# C-02_LvDDR3.net
KiCad netlist of a schematic drawn in Altium Designer
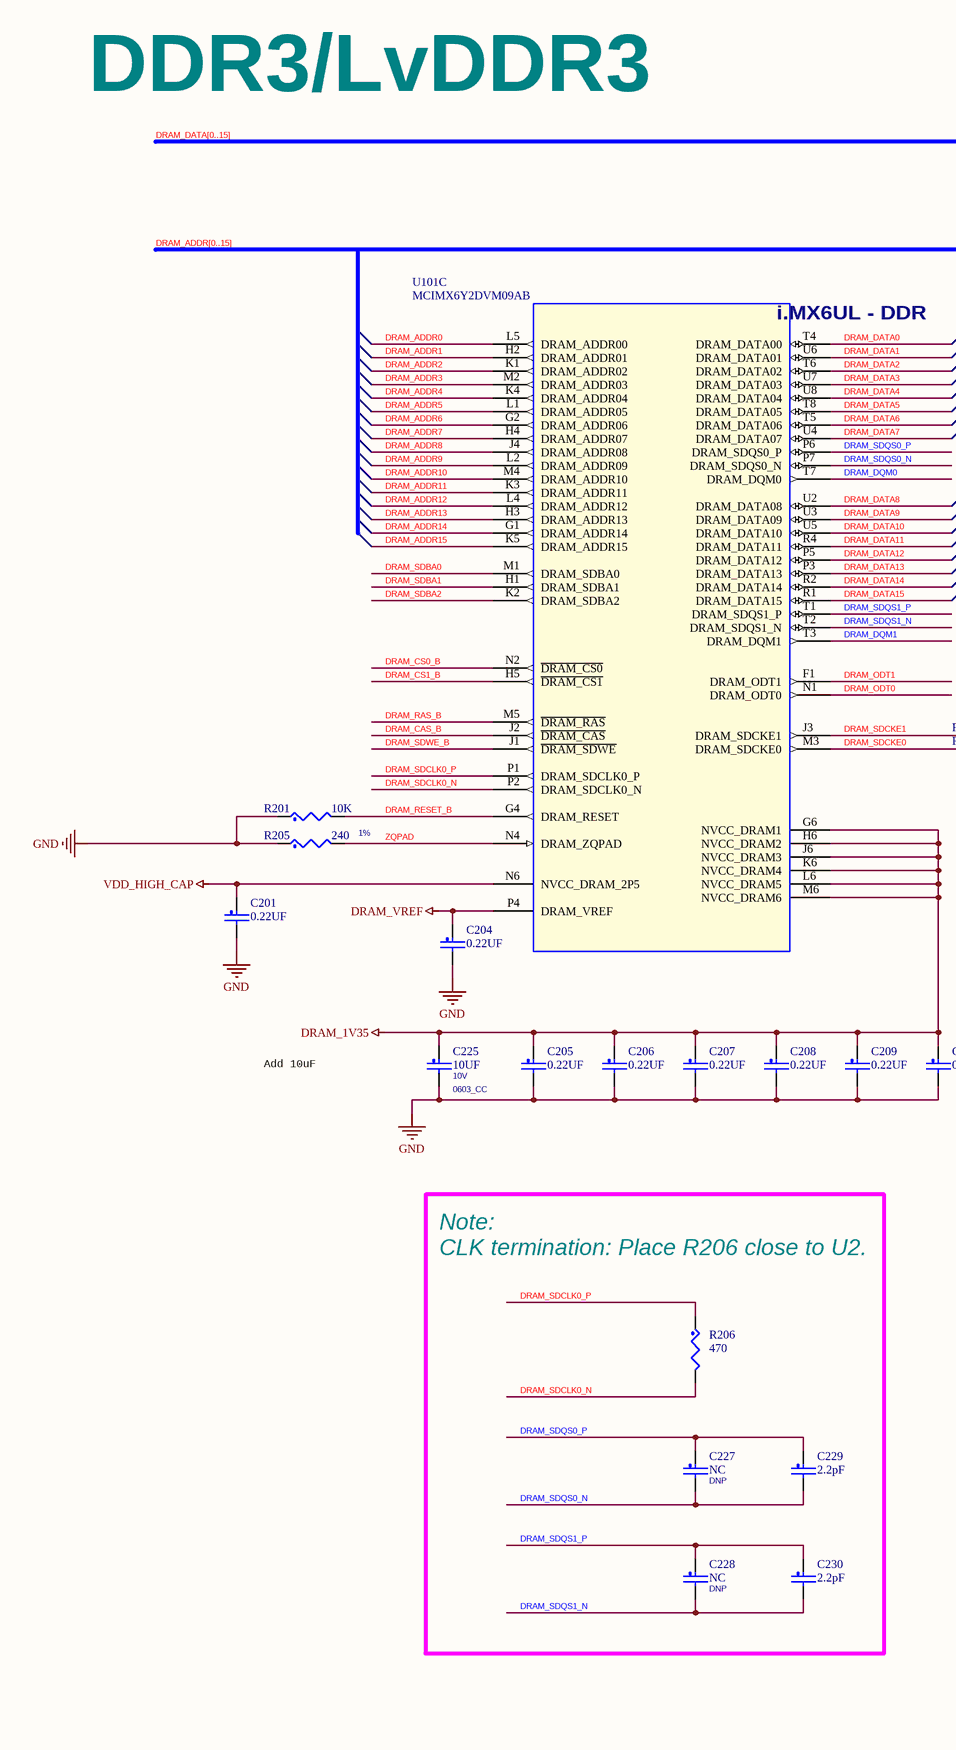
[diagram p0: C-02 LvDDR3.SchDoc, left]
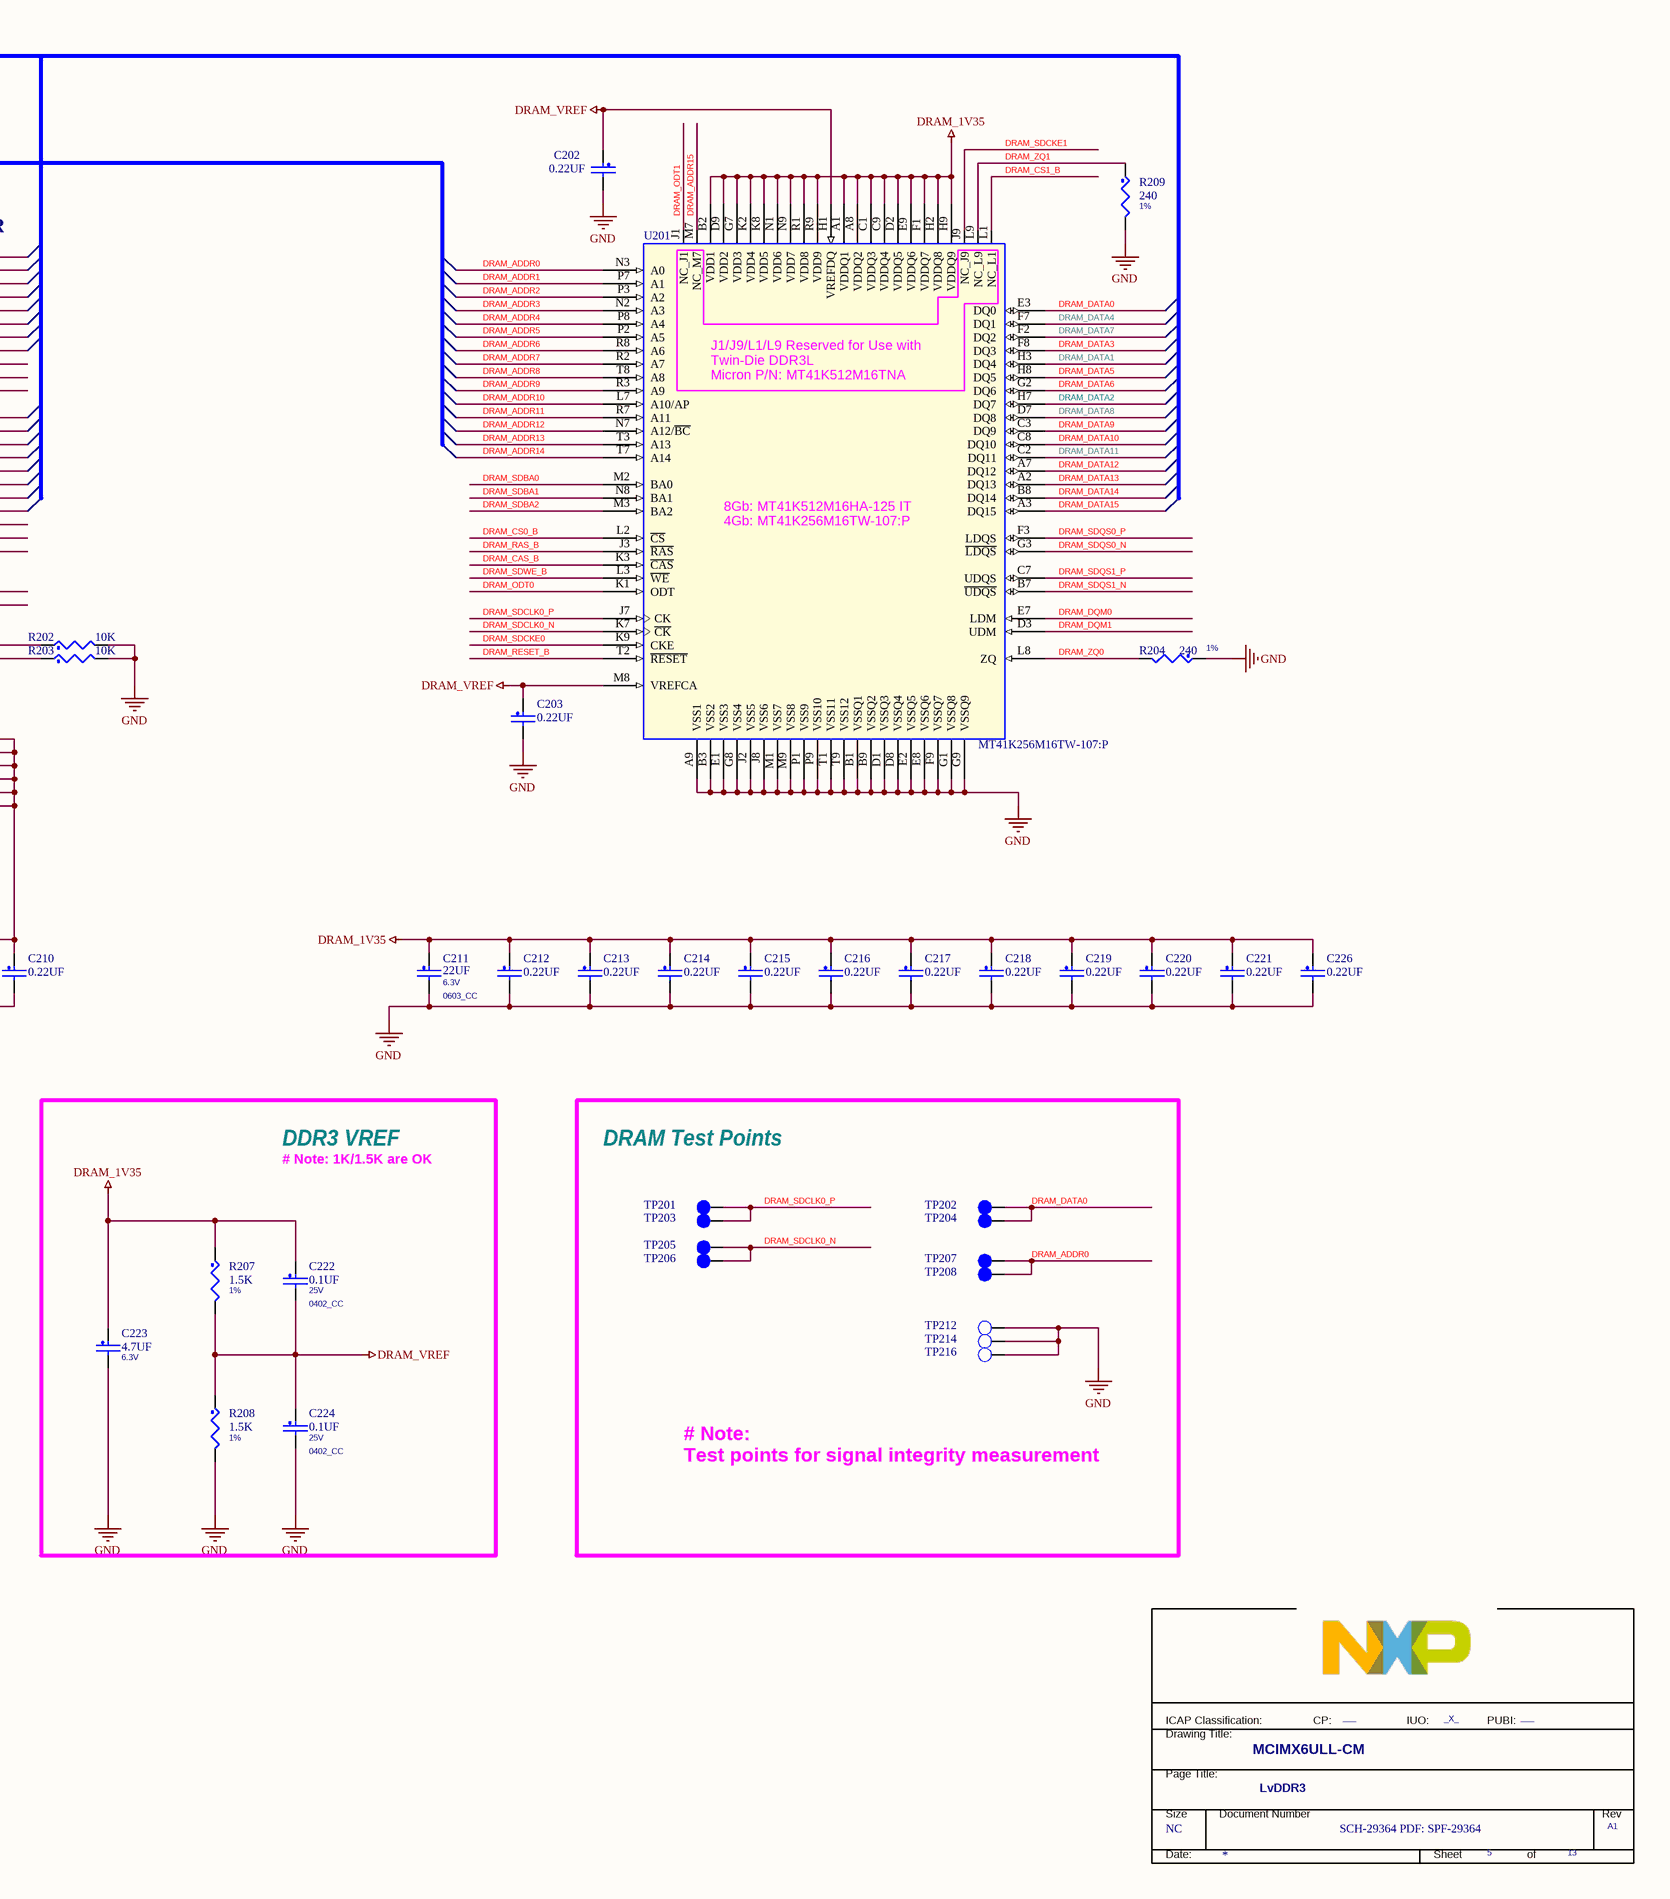
[diagram p1: C-02 LvDDR3.SchDoc, right]

(export (version "E")
  (design (tool "Eeschema 10.0.6"))
  (components
    (comp (ref "*")
      (value "TitleBlock_FS")
      (fields
        (field (name "PAGETITLE") "LvDDR3")
        (field (name "PAGE COUNT") "13")
        (field (name "PAGE NUMBER") "5")
        (field (name "PAGE SIZE") "NC")
        (field (name "TITLE") "MCIMX6ULL-CM")
        (field (name "REVCODE") "A1")
        (field (name "DOC") "SCH-29364 PDF: SPF-29364")
        (field (name "FCP") "___")
        (field (name "PUBI") "___")
        (field (name "FIUO") "_X_")
      )
      (libsource (lib "*") (part "TitleBlock_FS"))
    )
    (comp (ref "C201")
      (value "0.22UF")
      (footprint "0402T_C")
      (description "CAP CER 0.22UF 10V 10% X5R 0402")
      (fields (field (name "VOLTAGE") "10V") (field (name "TOLERANCE") "10%"))
      (libsource (lib "*") (part "CAP_NP"))
    )
    (comp (ref "C202")
      (value "0.22UF")
      (footprint "0402T_C")
      (description "CAP CER 0.22UF 10V 10% X5R 0402")
      (fields (field (name "TOLERANCE") "10%") (field (name "VOLTAGE") "10V"))
      (libsource (lib "*") (part "CAP_NP"))
    )
    (comp (ref "C203")
      (value "0.22UF")
      (footprint "0402T_C")
      (description "CAP CER 0.22UF 10V 10% X5R 0402")
      (fields (field (name "TOLERANCE") "10%") (field (name "VOLTAGE") "10V"))
      (libsource (lib "*") (part "CAP_NP"))
    )
    (comp (ref "C204")
      (value "0.22UF")
      (footprint "0402T_C")
      (description "CAP CER 0.22UF 10V 10% X5R 0402")
      (fields (field (name "TOLERANCE") "10%") (field (name "VOLTAGE") "10V"))
      (libsource (lib "*") (part "CAP_NP"))
    )
    (comp (ref "C205")
      (value "0.22UF")
      (footprint "0402T_C")
      (description "CAP CER 0.22UF 10V 10% X5R 0402")
      (fields (field (name "VOLTAGE") "10V") (field (name "TOLERANCE") "10%"))
      (libsource (lib "*") (part "CAP_NP"))
    )
    (comp (ref "C206")
      (value "0.22UF")
      (footprint "0402T_C")
      (description "CAP CER 0.22UF 10V 10% X5R 0402")
      (fields (field (name "VOLTAGE") "10V") (field (name "TOLERANCE") "10%"))
      (libsource (lib "*") (part "CAP_NP"))
    )
    (comp (ref "C207")
      (value "0.22UF")
      (footprint "0402T_C")
      (description "CAP CER 0.22UF 10V 10% X5R 0402")
      (fields (field (name "VOLTAGE") "10V") (field (name "TOLERANCE") "10%"))
      (libsource (lib "*") (part "CAP_NP"))
    )
    (comp (ref "C208")
      (value "0.22UF")
      (footprint "0402T_C")
      (description "CAP CER 0.22UF 10V 10% X5R 0402")
      (fields (field (name "VOLTAGE") "10V") (field (name "TOLERANCE") "10%"))
      (libsource (lib "*") (part "CAP_NP"))
    )
    (comp (ref "C209")
      (value "0.22UF")
      (footprint "0402T_C")
      (description "CAP CER 0.22UF 10V 10% X5R 0402")
      (fields (field (name "VOLTAGE") "10V") (field (name "TOLERANCE") "10%"))
      (libsource (lib "*") (part "CAP_NP"))
    )
    (comp (ref "C210")
      (value "0.22UF")
      (footprint "0402T_C")
      (description "CAP CER 0.22UF 10V 10% X5R 0402")
      (fields (field (name "TOLERANCE") "10%") (field (name "VOLTAGE") "10V"))
      (libsource (lib "*") (part "CAP_NP"))
    )
    (comp (ref "C211")
      (value "22UF")
      (footprint "0603_CC")
      (description "CAP CER 22UF 6.3V 20% X5R 0603")
      (fields
        (field (name "VOLTAGE RATING") "6.3V")
        (field (name "TOLERANCE") "20%")
        (field (name "VOLTAGE") "6.3V")
        (field (name "PCB FOOTPRINT") "0603_CC")
      )
      (libsource (lib "*") (part "CAP_NP"))
    )
    (comp (ref "C212")
      (value "0.22UF")
      (footprint "0402T_C")
      (description "CAP CER 0.22UF 10V 10% X5R 0402")
      (fields (field (name "VOLTAGE") "10V") (field (name "TOLERANCE") "10%"))
      (libsource (lib "*") (part "CAP_NP"))
    )
    (comp (ref "C213")
      (value "0.22UF")
      (footprint "0402T_C")
      (description "CAP CER 0.22UF 10V 10% X5R 0402")
      (fields (field (name "VOLTAGE") "10V") (field (name "TOLERANCE") "10%"))
      (libsource (lib "*") (part "CAP_NP"))
    )
    (comp (ref "C214")
      (value "0.22UF")
      (footprint "0402T_C")
      (description "CAP CER 0.22UF 10V 10% X5R 0402")
      (fields (field (name "VOLTAGE") "10V") (field (name "TOLERANCE") "10%"))
      (libsource (lib "*") (part "CAP_NP"))
    )
    (comp (ref "C215")
      (value "0.22UF")
      (footprint "0402T_C")
      (description "CAP CER 0.22UF 10V 10% X5R 0402")
      (fields (field (name "VOLTAGE") "10V") (field (name "TOLERANCE") "10%"))
      (libsource (lib "*") (part "CAP_NP"))
    )
    (comp (ref "C216")
      (value "0.22UF")
      (footprint "0402T_C")
      (description "CAP CER 0.22UF 10V 10% X5R 0402")
      (fields (field (name "VOLTAGE") "10V") (field (name "TOLERANCE") "10%"))
      (libsource (lib "*") (part "CAP_NP"))
    )
    (comp (ref "C217")
      (value "0.22UF")
      (footprint "0402T_C")
      (description "CAP CER 0.22UF 10V 10% X5R 0402")
      (fields (field (name "TOLERANCE") "10%") (field (name "VOLTAGE") "10V"))
      (libsource (lib "*") (part "CAP_NP"))
    )
    (comp (ref "C218")
      (value "0.22UF")
      (footprint "0402T_C")
      (description "CAP CER 0.22UF 10V 10% X5R 0402")
      (fields (field (name "TOLERANCE") "10%") (field (name "VOLTAGE") "10V"))
      (libsource (lib "*") (part "CAP_NP"))
    )
    (comp (ref "C219")
      (value "0.22UF")
      (footprint "0402T_C")
      (description "CAP CER 0.22UF 10V 10% X5R 0402")
      (fields (field (name "TOLERANCE") "10%") (field (name "VOLTAGE") "10V"))
      (libsource (lib "*") (part "CAP_NP"))
    )
    (comp (ref "C220")
      (value "0.22UF")
      (footprint "0402T_C")
      (description "CAP CER 0.22UF 10V 10% X5R 0402")
      (fields (field (name "TOLERANCE") "10%") (field (name "VOLTAGE") "10V"))
      (libsource (lib "*") (part "CAP_NP"))
    )
    (comp (ref "C221")
      (value "0.22UF")
      (footprint "0402T_C")
      (description "CAP CER 0.22UF 10V 10% X5R 0402")
      (fields (field (name "TOLERANCE") "10%") (field (name "VOLTAGE") "10V"))
      (libsource (lib "*") (part "CAP_NP"))
    )
    (comp (ref "C222")
      (value "0.1UF")
      (footprint "0402T_C")
      (description "CAP CER 0.1UF 25V 10% X5R 0402")
      (fields
        (field (name "TOLERANCE") "10%")
        (field (name "VOLTAGE") "25V")
        (field (name "PCB FOOTPRINT") "0402_CC")
      )
      (libsource (lib "*") (part "CAP_NP"))
    )
    (comp (ref "C223")
      (value "4.7UF")
      (footprint "0402T_C")
      (description "CAP CER 4.7UF 6.3V 20% X5R 0402")
      (fields
        (field (name "TOLERANCE") "20%")
        (field (name "VOLTAGE RATING") "6.3V")
        (field (name "VOLTAGE") "6.3V")
      )
      (libsource (lib "*") (part "CAP_NP"))
    )
    (comp (ref "C224")
      (value "0.1UF")
      (footprint "0402T_C")
      (description "CAP CER 0.1UF 25V 10% X5R 0402")
      (fields
        (field (name "TOLERANCE") "10%")
        (field (name "VOLTAGE") "25V")
        (field (name "PCB FOOTPRINT") "0402_CC")
      )
      (libsource (lib "*") (part "CAP_NP"))
    )
    (comp (ref "C225")
      (value "10UF")
      (footprint "0402T_C")
      (description "CAP CER 10UF 10V 20% X5R 0603")
      (fields (field (name "VOLTAGE") "10V") (field (name "PCB FOOTPRINT") "0603_CC"))
      (libsource (lib "*") (part "CAP_NP"))
    )
    (comp (ref "C226")
      (value "0.22UF")
      (footprint "0402T_C")
      (description "CAP CER 0.22UF 10V 10% X5R 0402")
      (fields (field (name "VOLTAGE") "10V") (field (name "TOLERANCE") "10%"))
      (libsource (lib "*") (part "CAP_NP"))
    )
    (comp (ref "C227")
      (value "NC")
      (footprint "0402T_C")
      (description "CAP CER 2.2pF 50V 0.25pF C0G 0402")
      (fields
        (field (name "ASSY_OPT") "DNP")
        (field (name "VOLTAGE") "50V")
        (field (name "TOLERANCE") "11.36%")
      )
      (libsource (lib "*") (part "CAP_NP"))
    )
    (comp (ref "C228")
      (value "NC")
      (footprint "0402T_C")
      (description "CAP CER 2.2pF 50V 0.25pF C0G 0402")
      (fields
        (field (name "ASSY_OPT") "DNP")
        (field (name "VOLTAGE") "50V")
        (field (name "TOLERANCE") "11.36%")
      )
      (libsource (lib "*") (part "CAP_NP"))
    )
    (comp (ref "C229")
      (value "2.2pF")
      (footprint "0402T_C")
      (description "CAP CER 2.2pF 50V 0.25pF C0G 0402")
      (fields (field (name "VOLTAGE") "50V") (field (name "TOLERANCE") "11.36%"))
      (libsource (lib "*") (part "CAP_NP"))
    )
    (comp (ref "C230")
      (value "2.2pF")
      (footprint "0402T_C")
      (description "CAP CER 2.2pF 50V 0.25pF C0G 0402")
      (fields (field (name "VOLTAGE") "50V") (field (name "TOLERANCE") "11.36%"))
      (libsource (lib "*") (part "CAP_NP"))
    )
    (comp (ref "R201")
      (value "10K")
      (footprint "0402T_C")
      (description "RES MF 10K 1/16W 5% 0402")
      (fields (field (name "TOLERANCE") "5%"))
      (libsource (lib "*") (part "RES"))
    )
    (comp (ref "R202")
      (value "10K")
      (footprint "0402T_C")
      (description "RES MF 10K 1/16W 5% 0402")
      (fields (field (name "TOLERANCE") "5%"))
      (libsource (lib "*") (part "RES"))
    )
    (comp (ref "R203")
      (value "10K")
      (footprint "0402T_C")
      (description "RES MF 10K 1/16W 5% 0402")
      (fields (field (name "TOLERANCE") "5%"))
      (libsource (lib "*") (part "RES"))
    )
    (comp (ref "R204")
      (value "240")
      (footprint "0402T_C")
      (description "RES MF 240 OHM 1/16W 1% 0402")
      (fields (field (name "TOLERANCE") "1%"))
      (libsource (lib "*") (part "RES"))
    )
    (comp (ref "R205")
      (value "240")
      (footprint "0402T_C")
      (description "RES MF 240 OHM 1/16W 1% 0402")
      (fields (field (name "TOLERANCE") "1%"))
      (libsource (lib "*") (part "RES"))
    )
    (comp (ref "R206")
      (value "470")
      (footprint "0402T_C")
      (description "RES MF 470 OHM 1/16W 5% 0402")
      (fields (field (name "TOLERANCE") "5%"))
      (libsource (lib "*") (part "RES"))
    )
    (comp (ref "R207")
      (value "1.5K")
      (footprint "0402T_C")
      (description "RES MF 1.5K 1/16W 1% 0402")
      (fields (field (name "TOLERANCE") "1%"))
      (libsource (lib "*") (part "RES"))
    )
    (comp (ref "R208")
      (value "1.5K")
      (footprint "0402T_C")
      (description "RES MF 1.5K 1/16W 1% 0402")
      (fields (field (name "TOLERANCE") "1%"))
      (libsource (lib "*") (part "RES"))
    )
    (comp (ref "R209")
      (value "240")
      (footprint "0402T_C")
      (description "RES MF 240 OHM 1/16W 1% 0402")
      (fields (field (name "TOLERANCE") "1%"))
      (libsource (lib "*") (part "RES"))
    )
    (comp (ref "TP201")
      (value "TPAD_015")
      (footprint "TPAD_015")
      (description "TEST POINT PAD 15MIL DIA SMT, NO PART TO ORDER")
      (libsource (lib "*") (part "TESTLOOP"))
    )
    (comp (ref "TP202")
      (value "TPAD_015")
      (footprint "TPAD_015")
      (description "TEST POINT PAD 15MIL DIA SMT, NO PART TO ORDER")
      (libsource (lib "*") (part "TESTLOOP"))
    )
    (comp (ref "TP203")
      (value "TPAD_015")
      (footprint "TPAD_015")
      (description "TEST POINT PAD 15MIL DIA SMT, NO PART TO ORDER")
      (libsource (lib "*") (part "TESTLOOP"))
    )
    (comp (ref "TP204")
      (value "TPAD_015")
      (footprint "TPAD_015")
      (description "TEST POINT PAD 15MIL DIA SMT, NO PART TO ORDER")
      (libsource (lib "*") (part "TESTLOOP"))
    )
    (comp (ref "TP205")
      (value "TPAD_015")
      (footprint "TPAD_015")
      (description "TEST POINT PAD 15MIL DIA SMT, NO PART TO ORDER")
      (libsource (lib "*") (part "TESTLOOP"))
    )
    (comp (ref "TP206")
      (value "TPAD_015")
      (footprint "TPAD_015")
      (description "TEST POINT PAD 15MIL DIA SMT, NO PART TO ORDER")
      (libsource (lib "*") (part "TESTLOOP"))
    )
    (comp (ref "TP207")
      (value "TPAD_015")
      (footprint "TPAD_015")
      (description "TEST POINT PAD 15MIL DIA SMT, NO PART TO ORDER")
      (libsource (lib "*") (part "TESTLOOP"))
    )
    (comp (ref "TP208")
      (value "TPAD_015")
      (footprint "TPAD_015")
      (description "TEST POINT PAD 15MIL DIA SMT, NO PART TO ORDER")
      (libsource (lib "*") (part "TESTLOOP"))
    )
    (comp (ref "TP212")
      (value "TP_35MIL")
      (footprint "testpoint_35mil")
      (description "TEST POINT PAD .035 SMT, no part to order")
      (libsource (lib "*") (part "T POINT R"))
    )
    (comp (ref "TP214")
      (value "TP_35MIL")
      (footprint "testpoint_35mil")
      (description "TEST POINT PAD .035 SMT, no part to order")
      (libsource (lib "*") (part "T POINT R"))
    )
    (comp (ref "TP216")
      (value "TP_35MIL")
      (footprint "testpoint_35mil")
      (description "TEST POINT PAD .035 SMT, no part to order")
      (libsource (lib "*") (part "T POINT R"))
    )
    (comp (ref "U101")
      (value "MCIMX6Y2DVM09AB")
      (footprint "BGA289_0P8_14X14")
      (description "IC CPU ARM COREA7 900MHZ 16BIT 3-3.6V PBGA289")
      (libsource (lib "*") (part "MCIMX6Y2DVM05AA_PBGA_289P"))
    )
    (comp (ref "U201")
      (value "MT41K256M16TW-107:P")
      (footprint "bga96_0p8_8p15x14p15")
      (description "IC MEM DDR3 SDRAM 256MX16 1.071NS 1.35V FBGA96")
      (libsource (lib "*") (part "MT41J256M16RE_FBGA96"))
    )
  )
  (nets
    (net (code "1") (name "/DRAM_ADDR0") (class "Default")
      (node (ref "TP207") (pin "1") (pinfunction "Pin1_1") (pintype "passive"))
      (node (ref "TP208") (pin "1") (pinfunction "Pin1_1") (pintype "passive"))
      (node (ref "U101") (pin "L5") (pinfunction "DRAM_ADDR00_L5") (pintype "output"))
      (node (ref "U201") (pin "N3") (pinfunction "A0_N3") (pintype "input"))
    )
    (net (code "2") (name "/DRAM_ADDR1") (class "Default")
      (node (ref "U101") (pin "H2") (pinfunction "DRAM_ADDR01_H2") (pintype "output"))
      (node (ref "U201") (pin "P7") (pinfunction "A1_P7") (pintype "input"))
    )
    (net (code "3") (name "/DRAM_ADDR2") (class "Default")
      (node (ref "U101") (pin "K1") (pinfunction "DRAM_ADDR02_K1") (pintype "output"))
      (node (ref "U201") (pin "P3") (pinfunction "A2_P3") (pintype "input"))
    )
    (net (code "4") (name "/DRAM_ADDR3") (class "Default")
      (node (ref "U101") (pin "M2") (pinfunction "DRAM_ADDR03_M2") (pintype "output"))
      (node (ref "U201") (pin "N2") (pinfunction "A3_N2") (pintype "input"))
    )
    (net (code "5") (name "/DRAM_ADDR4") (class "Default")
      (node (ref "U101") (pin "K4") (pinfunction "DRAM_ADDR04_K4") (pintype "output"))
      (node (ref "U201") (pin "P8") (pinfunction "A4_P8") (pintype "input"))
    )
    (net (code "6") (name "/DRAM_ADDR5") (class "Default")
      (node (ref "U101") (pin "L1") (pinfunction "DRAM_ADDR05_L1") (pintype "output"))
      (node (ref "U201") (pin "P2") (pinfunction "A5_P2") (pintype "input"))
    )
    (net (code "7") (name "/DRAM_ADDR6") (class "Default")
      (node (ref "U101") (pin "G2") (pinfunction "DRAM_ADDR06_G2") (pintype "output"))
      (node (ref "U201") (pin "R8") (pinfunction "A6_R8") (pintype "input"))
    )
    (net (code "8") (name "/DRAM_ADDR7") (class "Default")
      (node (ref "U101") (pin "H4") (pinfunction "DRAM_ADDR07_H4") (pintype "output"))
      (node (ref "U201") (pin "R2") (pinfunction "A7_R2") (pintype "input"))
    )
    (net (code "9") (name "/DRAM_ADDR8") (class "Default")
      (node (ref "U101") (pin "J4") (pinfunction "DRAM_ADDR08_J4") (pintype "output"))
      (node (ref "U201") (pin "T8") (pinfunction "A8_T8") (pintype "input"))
    )
    (net (code "10") (name "/DRAM_ADDR9") (class "Default")
      (node (ref "U101") (pin "L2") (pinfunction "DRAM_ADDR09_L2") (pintype "output"))
      (node (ref "U201") (pin "R3") (pinfunction "A9_R3") (pintype "input"))
    )
    (net (code "11") (name "/DRAM_ADDR10") (class "Default")
      (node (ref "U101") (pin "M4") (pinfunction "DRAM_ADDR10_M4") (pintype "output"))
      (node (ref "U201") (pin "L7") (pinfunction "A10/AP_L7") (pintype "input"))
    )
    (net (code "12") (name "/DRAM_ADDR11") (class "Default")
      (node (ref "U101") (pin "K3") (pinfunction "DRAM_ADDR11_K3") (pintype "output"))
      (node (ref "U201") (pin "R7") (pinfunction "A11_R7") (pintype "input"))
    )
    (net (code "13") (name "/DRAM_ADDR12") (class "Default")
      (node (ref "U101") (pin "L4") (pinfunction "DRAM_ADDR12_L4") (pintype "output"))
      (node (ref "U201") (pin "N7") (pinfunction "A12/~{BC}_N7") (pintype "input"))
    )
    (net (code "14") (name "/DRAM_ADDR13") (class "Default")
      (node (ref "U101") (pin "H3") (pinfunction "DRAM_ADDR13_H3") (pintype "output"))
      (node (ref "U201") (pin "T3") (pinfunction "A13_T3") (pintype "input"))
    )
    (net (code "15") (name "/DRAM_ADDR14") (class "Default")
      (node (ref "U101") (pin "G1") (pinfunction "DRAM_ADDR14_G1") (pintype "output"))
      (node (ref "U201") (pin "T7") (pinfunction "A14_T7") (pintype "input"))
    )
    (net (code "16") (name "/DRAM_ADDR15") (class "Default")
      (node (ref "U101") (pin "K5") (pinfunction "DRAM_ADDR15_K5") (pintype "output"))
      (node (ref "U201") (pin "M7") (pinfunction "NC_M7_M7") (pintype "passive"))
    )
    (net (code "18") (name "/DRAM_CAS_B") (class "Default")
      (node (ref "U101") (pin "J2") (pinfunction "~{DRAM_CAS}_J2") (pintype "output"))
      (node (ref "U201") (pin "K3") (pinfunction "~{CAS}_K3") (pintype "input"))
    )
    (net (code "19") (name "/DRAM_CS0_B") (class "Default")
      (node (ref "U101") (pin "N2") (pinfunction "~{DRAM_CS0}_N2") (pintype "output"))
      (node (ref "U201") (pin "L2") (pinfunction "~{CS}_L2") (pintype "input"))
    )
    (net (code "20") (name "/DRAM_CS1_B") (class "Default")
      (node (ref "U101") (pin "H5") (pinfunction "~{DRAM_CS1}_H5") (pintype "output"))
      (node (ref "U201") (pin "L1") (pinfunction "NC_L1_L1") (pintype "passive"))
    )
    (net (code "21") (name "/DRAM_DATA0") (class "Default")
      (node (ref "TP202") (pin "1") (pinfunction "Pin1_1") (pintype "passive"))
      (node (ref "TP204") (pin "1") (pinfunction "Pin1_1") (pintype "passive"))
      (node (ref "U101") (pin "T4") (pinfunction "DRAM_DATA00_T4") (pintype "bidirectional"))
      (node (ref "U201") (pin "E3") (pinfunction "DQ0_E3") (pintype "bidirectional"))
    )
    (net (code "22") (name "/DRAM_DATA1") (class "Default")
      (node (ref "U101") (pin "U6") (pinfunction "DRAM_DATA01_U6") (pintype "bidirectional"))
      (node (ref "U201") (pin "H3") (pinfunction "DQ4_H3") (pintype "bidirectional"))
    )
    (net (code "23") (name "/DRAM_DATA2") (class "Default")
      (node (ref "U101") (pin "T6") (pinfunction "DRAM_DATA02_T6") (pintype "bidirectional"))
      (node (ref "U201") (pin "H7") (pinfunction "DQ7_H7") (pintype "bidirectional"))
    )
    (net (code "24") (name "/DRAM_DATA3") (class "Default")
      (node (ref "U101") (pin "U7") (pinfunction "DRAM_DATA03_U7") (pintype "bidirectional"))
      (node (ref "U201") (pin "F8") (pinfunction "DQ3_F8") (pintype "bidirectional"))
    )
    (net (code "25") (name "/DRAM_DATA4") (class "Default")
      (node (ref "U101") (pin "U8") (pinfunction "DRAM_DATA04_U8") (pintype "bidirectional"))
      (node (ref "U201") (pin "F7") (pinfunction "DQ1_F7") (pintype "bidirectional"))
    )
    (net (code "26") (name "/DRAM_DATA5") (class "Default")
      (node (ref "U101") (pin "T8") (pinfunction "DRAM_DATA05_T8") (pintype "bidirectional"))
      (node (ref "U201") (pin "H8") (pinfunction "DQ5_H8") (pintype "bidirectional"))
    )
    (net (code "27") (name "/DRAM_DATA6") (class "Default")
      (node (ref "U101") (pin "T5") (pinfunction "DRAM_DATA06_T5") (pintype "bidirectional"))
      (node (ref "U201") (pin "G2") (pinfunction "DQ6_G2") (pintype "bidirectional"))
    )
    (net (code "28") (name "/DRAM_DATA7") (class "Default")
      (node (ref "U101") (pin "U4") (pinfunction "DRAM_DATA07_U4") (pintype "bidirectional"))
      (node (ref "U201") (pin "F2") (pinfunction "DQ2_F2") (pintype "bidirectional"))
    )
    (net (code "29") (name "/DRAM_DATA8") (class "Default")
      (node (ref "U101") (pin "U2") (pinfunction "DRAM_DATA08_U2") (pintype "bidirectional"))
      (node (ref "U201") (pin "D7") (pinfunction "DQ8_D7") (pintype "bidirectional"))
    )
    (net (code "30") (name "/DRAM_DATA9") (class "Default")
      (node (ref "U101") (pin "U3") (pinfunction "DRAM_DATA09_U3") (pintype "bidirectional"))
      (node (ref "U201") (pin "C3") (pinfunction "DQ9_C3") (pintype "bidirectional"))
    )
    (net (code "31") (name "/DRAM_DATA10") (class "Default")
      (node (ref "U101") (pin "U5") (pinfunction "DRAM_DATA10_U5") (pintype "bidirectional"))
      (node (ref "U201") (pin "C8") (pinfunction "DQ10_C8") (pintype "bidirectional"))
    )
    (net (code "32") (name "/DRAM_DATA11") (class "Default")
      (node (ref "U101") (pin "R4") (pinfunction "DRAM_DATA11_R4") (pintype "bidirectional"))
      (node (ref "U201") (pin "C2") (pinfunction "DQ11_C2") (pintype "bidirectional"))
    )
    (net (code "33") (name "/DRAM_DATA12") (class "Default")
      (node (ref "U101") (pin "P5") (pinfunction "DRAM_DATA12_P5") (pintype "bidirectional"))
      (node (ref "U201") (pin "A7") (pinfunction "DQ12_A7") (pintype "bidirectional"))
    )
    (net (code "34") (name "/DRAM_DATA13") (class "Default")
      (node (ref "U101") (pin "P3") (pinfunction "DRAM_DATA13_P3") (pintype "bidirectional"))
      (node (ref "U201") (pin "A2") (pinfunction "DQ13_A2") (pintype "bidirectional"))
    )
    (net (code "35") (name "/DRAM_DATA14") (class "Default")
      (node (ref "U101") (pin "R2") (pinfunction "DRAM_DATA14_R2") (pintype "bidirectional"))
      (node (ref "U201") (pin "B8") (pinfunction "DQ14_B8") (pintype "bidirectional"))
    )
    (net (code "36") (name "/DRAM_DATA15") (class "Default")
      (node (ref "U101") (pin "R1") (pinfunction "DRAM_DATA15_R1") (pintype "bidirectional"))
      (node (ref "U201") (pin "A3") (pinfunction "DQ15_A3") (pintype "bidirectional"))
    )
    (net (code "38") (name "/DRAM_DQM0") (class "Default")
      (node (ref "U101") (pin "T7") (pinfunction "DRAM_DQM0_T7") (pintype "output"))
      (node (ref "U201") (pin "E7") (pinfunction "LDM_E7") (pintype "input"))
    )
    (net (code "39") (name "/DRAM_DQM1") (class "Default")
      (node (ref "U101") (pin "T3") (pinfunction "DRAM_DQM1_T3") (pintype "output"))
      (node (ref "U201") (pin "D3") (pinfunction "UDM_D3") (pintype "input"))
    )
    (net (code "40") (name "/DRAM_ODT0") (class "Default")
      (node (ref "U101") (pin "N1") (pinfunction "DRAM_ODT0_N1") (pintype "output"))
      (node (ref "U201") (pin "K1") (pinfunction "ODT_K1") (pintype "input"))
    )
    (net (code "41") (name "/DRAM_ODT1") (class "Default")
      (node (ref "U101") (pin "F1") (pinfunction "DRAM_ODT1_F1") (pintype "output"))
      (node (ref "U201") (pin "J1") (pinfunction "NC_J1_J1") (pintype "passive"))
    )
    (net (code "42") (name "/DRAM_RAS_B") (class "Default")
      (node (ref "U101") (pin "M5") (pinfunction "~{DRAM_RAS}_M5") (pintype "output"))
      (node (ref "U201") (pin "J3") (pinfunction "~{RAS}_J3") (pintype "input"))
    )
    (net (code "43") (name "/DRAM_RESET_B") (class "Default")
      (node (ref "R201") (pin "2") (pinfunction "2_2") (pintype "passive"))
      (node (ref "U101") (pin "G4") (pinfunction "DRAM_RESET_G4") (pintype "output"))
      (node (ref "U201") (pin "T2") (pinfunction "~{RESET}_T2") (pintype "input"))
    )
    (net (code "44") (name "/DRAM_SDBA0") (class "Default")
      (node (ref "U101") (pin "M1") (pinfunction "DRAM_SDBA0_M1") (pintype "output"))
      (node (ref "U201") (pin "M2") (pinfunction "BA0_M2") (pintype "input"))
    )
    (net (code "45") (name "/DRAM_SDBA1") (class "Default")
      (node (ref "U101") (pin "H1") (pinfunction "DRAM_SDBA1_H1") (pintype "output"))
      (node (ref "U201") (pin "N8") (pinfunction "BA1_N8") (pintype "input"))
    )
    (net (code "46") (name "/DRAM_SDBA2") (class "Default")
      (node (ref "U101") (pin "K2") (pinfunction "DRAM_SDBA2_K2") (pintype "output"))
      (node (ref "U201") (pin "M3") (pinfunction "BA2_M3") (pintype "input"))
    )
    (net (code "47") (name "/DRAM_SDCKE0") (class "Default")
      (node (ref "R203") (pin "1") (pinfunction "1_1") (pintype "passive"))
      (node (ref "U101") (pin "M3") (pinfunction "DRAM_SDCKE0_M3") (pintype "output"))
      (node (ref "U201") (pin "K9") (pinfunction "CKE_K9") (pintype "input"))
    )
    (net (code "48") (name "/DRAM_SDCKE1") (class "Default")
      (node (ref "R202") (pin "1") (pinfunction "1_1") (pintype "passive"))
      (node (ref "U101") (pin "J3") (pinfunction "DRAM_SDCKE1_J3") (pintype "output"))
      (node (ref "U201") (pin "J9") (pinfunction "NC_J9_J9") (pintype "passive"))
    )
    (net (code "49") (name "/DRAM_SDCLK0_N") (class "Default")
      (node (ref "R206") (pin "2") (pinfunction "2_2") (pintype "passive"))
      (node (ref "TP205") (pin "1") (pinfunction "Pin1_1") (pintype "passive"))
      (node (ref "TP206") (pin "1") (pinfunction "Pin1_1") (pintype "passive"))
      (node (ref "U101") (pin "P2") (pinfunction "DRAM_SDCLK0_N_P2") (pintype "output"))
      (node (ref "U201") (pin "K7") (pinfunction "~{CK}_K7") (pintype "input"))
    )
    (net (code "50") (name "/DRAM_SDCLK0_P") (class "Default")
      (node (ref "R206") (pin "1") (pinfunction "1_1") (pintype "passive"))
      (node (ref "TP201") (pin "1") (pinfunction "Pin1_1") (pintype "passive"))
      (node (ref "TP203") (pin "1") (pinfunction "Pin1_1") (pintype "passive"))
      (node (ref "U101") (pin "P1") (pinfunction "DRAM_SDCLK0_P_P1") (pintype "output"))
      (node (ref "U201") (pin "J7") (pinfunction "CK_J7") (pintype "input"))
    )
    (net (code "51") (name "/DRAM_SDQS0_N") (class "Default")
      (node (ref "C227") (pin "2") (pinfunction "2_2") (pintype "passive"))
      (node (ref "C229") (pin "2") (pinfunction "2_2") (pintype "passive"))
      (node (ref "U101") (pin "P7") (pinfunction "DRAM_SDQS0_N_P7") (pintype "bidirectional"))
      (node (ref "U201") (pin "G3") (pinfunction "~{LDQS}_G3") (pintype "bidirectional"))
    )
    (net (code "52") (name "/DRAM_SDQS0_P") (class "Default")
      (node (ref "C227") (pin "1") (pinfunction "1_1") (pintype "passive"))
      (node (ref "C229") (pin "1") (pinfunction "1_1") (pintype "passive"))
      (node (ref "U101") (pin "P6") (pinfunction "DRAM_SDQS0_P_P6") (pintype "bidirectional"))
      (node (ref "U201") (pin "F3") (pinfunction "LDQS_F3") (pintype "bidirectional"))
    )
    (net (code "53") (name "/DRAM_SDQS1_N") (class "Default")
      (node (ref "C228") (pin "2") (pinfunction "2_2") (pintype "passive"))
      (node (ref "C230") (pin "2") (pinfunction "2_2") (pintype "passive"))
      (node (ref "U101") (pin "T2") (pinfunction "DRAM_SDQS1_N_T2") (pintype "bidirectional"))
      (node (ref "U201") (pin "B7") (pinfunction "~{UDQS}_B7") (pintype "bidirectional"))
    )
    (net (code "54") (name "/DRAM_SDQS1_P") (class "Default")
      (node (ref "C228") (pin "1") (pinfunction "1_1") (pintype "passive"))
      (node (ref "C230") (pin "1") (pinfunction "1_1") (pintype "passive"))
      (node (ref "U101") (pin "T1") (pinfunction "DRAM_SDQS1_P_T1") (pintype "bidirectional"))
      (node (ref "U201") (pin "C7") (pinfunction "UDQS_C7") (pintype "bidirectional"))
    )
    (net (code "55") (name "/DRAM_SDWE_B") (class "Default")
      (node (ref "U101") (pin "J1") (pinfunction "~{DRAM_SDWE}_J1") (pintype "output"))
      (node (ref "U201") (pin "L3") (pinfunction "~{WE}_L3") (pintype "input"))
    )
    (net (code "56") (name "/DRAM_ZQ0") (class "Default")
      (node (ref "R204") (pin "2") (pinfunction "2_2") (pintype "passive"))
      (node (ref "U201") (pin "L8") (pinfunction "ZQ_L8") (pintype "input"))
    )
    (net (code "57") (name "/DRAM_ZQ1") (class "Default")
      (node (ref "R209") (pin "1") (pinfunction "1_1") (pintype "passive"))
      (node (ref "U201") (pin "L9") (pinfunction "NC_L9_L9") (pintype "passive"))
    )
    (net (code "58") (name "/ZQPAD") (class "Default")
      (node (ref "R205") (pin "2") (pinfunction "2_2") (pintype "passive"))
      (node (ref "U101") (pin "N4") (pinfunction "DRAM_ZQPAD_N4") (pintype "input"))
    )
    (net (code "59") (name "DRAM_1V35") (class "Default")
      (node (ref "C205") (pin "1") (pinfunction "1_1") (pintype "passive"))
      (node (ref "C206") (pin "1") (pinfunction "1_1") (pintype "passive"))
      (node (ref "C207") (pin "1") (pinfunction "1_1") (pintype "passive"))
      (node (ref "C208") (pin "1") (pinfunction "1_1") (pintype "passive"))
      (node (ref "C209") (pin "1") (pinfunction "1_1") (pintype "passive"))
      (node (ref "C210") (pin "1") (pinfunction "1_1") (pintype "passive"))
      (node (ref "C211") (pin "1") (pinfunction "1_1") (pintype "passive"))
      (node (ref "C212") (pin "1") (pinfunction "1_1") (pintype "passive"))
      (node (ref "C213") (pin "1") (pinfunction "1_1") (pintype "passive"))
      (node (ref "C214") (pin "1") (pinfunction "1_1") (pintype "passive"))
      (node (ref "C215") (pin "1") (pinfunction "1_1") (pintype "passive"))
      (node (ref "C216") (pin "1") (pinfunction "1_1") (pintype "passive"))
      (node (ref "C217") (pin "1") (pinfunction "1_1") (pintype "passive"))
      (node (ref "C218") (pin "1") (pinfunction "1_1") (pintype "passive"))
      (node (ref "C219") (pin "1") (pinfunction "1_1") (pintype "passive"))
      (node (ref "C220") (pin "1") (pinfunction "1_1") (pintype "passive"))
      (node (ref "C221") (pin "1") (pinfunction "1_1") (pintype "passive"))
      (node (ref "C222") (pin "1") (pinfunction "1_1") (pintype "passive"))
      (node (ref "C223") (pin "1") (pinfunction "1_1") (pintype "passive"))
      (node (ref "C225") (pin "1") (pinfunction "1_1") (pintype "passive"))
      (node (ref "C226") (pin "1") (pinfunction "1_1") (pintype "passive"))
      (node (ref "R207") (pin "1") (pinfunction "1_1") (pintype "passive"))
      (node (ref "U101") (pin "G6") (pinfunction "NVCC_DRAM1_G6") (pintype "power_in"))
      (node (ref "U101") (pin "H6") (pinfunction "NVCC_DRAM2_H6") (pintype "power_in"))
      (node (ref "U101") (pin "J6") (pinfunction "NVCC_DRAM3_J6") (pintype "power_in"))
      (node (ref "U101") (pin "K6") (pinfunction "NVCC_DRAM4_K6") (pintype "power_in"))
      (node (ref "U101") (pin "L6") (pinfunction "NVCC_DRAM5_L6") (pintype "power_in"))
      (node (ref "U101") (pin "M6") (pinfunction "NVCC_DRAM6_M6") (pintype "power_in"))
      (node (ref "U201") (pin "A1") (pinfunction "VDDQ1_A1") (pintype "power_in"))
      (node (ref "U201") (pin "A8") (pinfunction "VDDQ2_A8") (pintype "power_in"))
      (node (ref "U201") (pin "B2") (pinfunction "VDD1_B2") (pintype "power_in"))
      (node (ref "U201") (pin "C1") (pinfunction "VDDQ3_C1") (pintype "power_in"))
      (node (ref "U201") (pin "C9") (pinfunction "VDDQ4_C9") (pintype "power_in"))
      (node (ref "U201") (pin "D2") (pinfunction "VDDQ5_D2") (pintype "power_in"))
      (node (ref "U201") (pin "D9") (pinfunction "VDD2_D9") (pintype "power_in"))
      (node (ref "U201") (pin "E9") (pinfunction "VDDQ6_E9") (pintype "power_in"))
      (node (ref "U201") (pin "F1") (pinfunction "VDDQ7_F1") (pintype "power_in"))
      (node (ref "U201") (pin "G7") (pinfunction "VDD3_G7") (pintype "power_in"))
      (node (ref "U201") (pin "H2") (pinfunction "VDDQ8_H2") (pintype "power_in"))
      (node (ref "U201") (pin "H9") (pinfunction "VDDQ9_H9") (pintype "power_in"))
      (node (ref "U201") (pin "K2") (pinfunction "VDD4_K2") (pintype "power_in"))
      (node (ref "U201") (pin "K8") (pinfunction "VDD5_K8") (pintype "power_in"))
      (node (ref "U201") (pin "N1") (pinfunction "VDD6_N1") (pintype "power_in"))
      (node (ref "U201") (pin "N9") (pinfunction "VDD7_N9") (pintype "power_in"))
      (node (ref "U201") (pin "R1") (pinfunction "VDD8_R1") (pintype "power_in"))
      (node (ref "U201") (pin "R9") (pinfunction "VDD9_R9") (pintype "power_in"))
    )
    (net (code "60") (name "DRAM_VREF") (class "Default")
      (node (ref "C202") (pin "1") (pinfunction "1_1") (pintype "passive"))
      (node (ref "C203") (pin "1") (pinfunction "1_1") (pintype "passive"))
      (node (ref "C204") (pin "1") (pinfunction "1_1") (pintype "passive"))
      (node (ref "C222") (pin "2") (pinfunction "2_2") (pintype "passive"))
      (node (ref "C224") (pin "1") (pinfunction "1_1") (pintype "passive"))
      (node (ref "R207") (pin "2") (pinfunction "2_2") (pintype "passive"))
      (node (ref "R208") (pin "1") (pinfunction "1_1") (pintype "passive"))
      (node (ref "U101") (pin "P4") (pinfunction "DRAM_VREF_P4") (pintype "power_in"))
      (node (ref "U201") (pin "H1") (pinfunction "VREFDQ_H1") (pintype "input"))
      (node (ref "U201") (pin "M8") (pinfunction "VREFCA_M8") (pintype "input"))
    )
    (net (code "61") (name "GND") (class "Default")
      (node (ref "C201") (pin "2") (pinfunction "2_2") (pintype "passive"))
      (node (ref "C202") (pin "2") (pinfunction "2_2") (pintype "passive"))
      (node (ref "C203") (pin "2") (pinfunction "2_2") (pintype "passive"))
      (node (ref "C204") (pin "2") (pinfunction "2_2") (pintype "passive"))
      (node (ref "C205") (pin "2") (pinfunction "2_2") (pintype "passive"))
      (node (ref "C206") (pin "2") (pinfunction "2_2") (pintype "passive"))
      (node (ref "C207") (pin "2") (pinfunction "2_2") (pintype "passive"))
      (node (ref "C208") (pin "2") (pinfunction "2_2") (pintype "passive"))
      (node (ref "C209") (pin "2") (pinfunction "2_2") (pintype "passive"))
      (node (ref "C210") (pin "2") (pinfunction "2_2") (pintype "passive"))
      (node (ref "C211") (pin "2") (pinfunction "2_2") (pintype "passive"))
      (node (ref "C212") (pin "2") (pinfunction "2_2") (pintype "passive"))
      (node (ref "C213") (pin "2") (pinfunction "2_2") (pintype "passive"))
      (node (ref "C214") (pin "2") (pinfunction "2_2") (pintype "passive"))
      (node (ref "C215") (pin "2") (pinfunction "2_2") (pintype "passive"))
      (node (ref "C216") (pin "2") (pinfunction "2_2") (pintype "passive"))
      (node (ref "C217") (pin "2") (pinfunction "2_2") (pintype "passive"))
      (node (ref "C218") (pin "2") (pinfunction "2_2") (pintype "passive"))
      (node (ref "C219") (pin "2") (pinfunction "2_2") (pintype "passive"))
      (node (ref "C220") (pin "2") (pinfunction "2_2") (pintype "passive"))
      (node (ref "C221") (pin "2") (pinfunction "2_2") (pintype "passive"))
      (node (ref "C223") (pin "2") (pinfunction "2_2") (pintype "passive"))
      (node (ref "C224") (pin "2") (pinfunction "2_2") (pintype "passive"))
      (node (ref "C225") (pin "2") (pinfunction "2_2") (pintype "passive"))
      (node (ref "C226") (pin "2") (pinfunction "2_2") (pintype "passive"))
      (node (ref "R201") (pin "1") (pinfunction "1_1") (pintype "passive"))
      (node (ref "R202") (pin "2") (pinfunction "2_2") (pintype "passive"))
      (node (ref "R203") (pin "2") (pinfunction "2_2") (pintype "passive"))
      (node (ref "R204") (pin "1") (pinfunction "1_1") (pintype "passive"))
      (node (ref "R205") (pin "1") (pinfunction "1_1") (pintype "passive"))
      (node (ref "R208") (pin "2") (pinfunction "2_2") (pintype "passive"))
      (node (ref "R209") (pin "2") (pinfunction "2_2") (pintype "passive"))
      (node (ref "TP212") (pin "1") (pinfunction "TP_1") (pintype "passive"))
      (node (ref "TP214") (pin "1") (pinfunction "TP_1") (pintype "passive"))
      (node (ref "TP216") (pin "1") (pinfunction "TP_1") (pintype "passive"))
      (node (ref "U201") (pin "A9") (pinfunction "VSS1_A9") (pintype "power_in"))
      (node (ref "U201") (pin "B1") (pinfunction "VSSQ1_B1") (pintype "power_in"))
      (node (ref "U201") (pin "B3") (pinfunction "VSS2_B3") (pintype "power_in"))
      (node (ref "U201") (pin "B9") (pinfunction "VSSQ2_B9") (pintype "power_in"))
      (node (ref "U201") (pin "D1") (pinfunction "VSSQ3_D1") (pintype "power_in"))
      (node (ref "U201") (pin "D8") (pinfunction "VSSQ4_D8") (pintype "power_in"))
      (node (ref "U201") (pin "E1") (pinfunction "VSS3_E1") (pintype "power_in"))
      (node (ref "U201") (pin "E2") (pinfunction "VSSQ5_E2") (pintype "power_in"))
      (node (ref "U201") (pin "E8") (pinfunction "VSSQ6_E8") (pintype "power_in"))
      (node (ref "U201") (pin "F9") (pinfunction "VSSQ7_F9") (pintype "power_in"))
      (node (ref "U201") (pin "G1") (pinfunction "VSSQ8_G1") (pintype "power_in"))
      (node (ref "U201") (pin "G8") (pinfunction "VSS4_G8") (pintype "power_in"))
      (node (ref "U201") (pin "G9") (pinfunction "VSSQ9_G9") (pintype "power_in"))
      (node (ref "U201") (pin "J2") (pinfunction "VSS5_J2") (pintype "power_in"))
      (node (ref "U201") (pin "J8") (pinfunction "VSS6_J8") (pintype "power_in"))
      (node (ref "U201") (pin "M1") (pinfunction "VSS7_M1") (pintype "power_in"))
      (node (ref "U201") (pin "M9") (pinfunction "VSS8_M9") (pintype "power_in"))
      (node (ref "U201") (pin "P1") (pinfunction "VSS9_P1") (pintype "power_in"))
      (node (ref "U201") (pin "P9") (pinfunction "VSS10_P9") (pintype "power_in"))
      (node (ref "U201") (pin "T1") (pinfunction "VSS11_T1") (pintype "power_in"))
      (node (ref "U201") (pin "T9") (pinfunction "VSS12_T9") (pintype "power_in"))
    )
    (net (code "62") (name "VDD_HIGH_CAP") (class "Default")
      (node (ref "C201") (pin "1") (pinfunction "1_1") (pintype "passive"))
      (node (ref "U101") (pin "N6") (pinfunction "NVCC_DRAM_2P5_N6") (pintype "power_in"))
    )
  )
)
